# pcb3.net
KiCad netlist of a schematic drawn in EAGLE
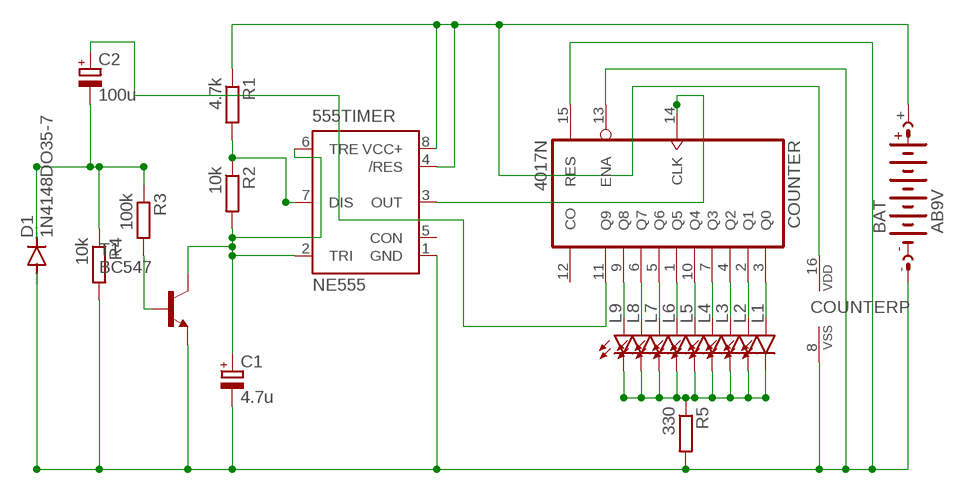
[diagram p0: schematic, sheet 1]

(export (version "E")
  (design (tool "Eeschema 10.0.6"))
  (components
    (comp (ref "555TIMER")
      (value "NE555")
      (footprint "eagle-import:DIL-08")
      (fields (field (name "MF") "Arrow Electronics") (field (name "MPN") "NE555N"))
      (libsource (lib "eagle-import") (part "NE555"))
    )
    (comp (ref "BAT")
      (value "AB9V")
      (footprint "eagle-import:AB9V")
      (libsource (lib "eagle-import") (part "AB9V"))
    )
    (comp (ref "C1")
      (value "4.7u")
      (footprint "eagle-import:E2,5-5")
      (libsource (lib "eagle-import") (part "CPOL-EUE2.5-5"))
    )
    (comp (ref "C2")
      (value "100u")
      (footprint "eagle-import:E2,5-5")
      (libsource (lib "eagle-import") (part "CPOL-EUE2.5-5"))
    )
    (comp (ref "COUNTER")
      (value "4017N")
      (footprint "eagle-import:DIL16")
      (libsource (lib "eagle-import") (part "4017N"))
    )
    (comp (ref "D1")
      (value "1N4148DO35-7")
      (footprint "eagle-import:DO35-7")
      (libsource (lib "eagle-import") (part "1N4148DO35-7"))
    )
    (comp (ref "L1")
      (value "LED5MM")
      (footprint "eagle-import:LED5MM")
      (libsource (lib "eagle-import") (part "LED5MM"))
    )
    (comp (ref "L2")
      (value "LED5MM")
      (footprint "eagle-import:LED5MM")
      (libsource (lib "eagle-import") (part "LED5MM"))
    )
    (comp (ref "L3")
      (value "LED5MM")
      (footprint "eagle-import:LED5MM")
      (libsource (lib "eagle-import") (part "LED5MM"))
    )
    (comp (ref "L4")
      (value "LED5MM")
      (footprint "eagle-import:LED5MM")
      (libsource (lib "eagle-import") (part "LED5MM"))
    )
    (comp (ref "L5")
      (value "LED5MM")
      (footprint "eagle-import:LED5MM")
      (libsource (lib "eagle-import") (part "LED5MM"))
    )
    (comp (ref "L6")
      (value "LED5MM")
      (footprint "eagle-import:LED5MM")
      (libsource (lib "eagle-import") (part "LED5MM"))
    )
    (comp (ref "L7")
      (value "LED5MM")
      (footprint "eagle-import:LED5MM")
      (libsource (lib "eagle-import") (part "LED5MM"))
    )
    (comp (ref "L8")
      (value "LED5MM")
      (footprint "eagle-import:LED5MM")
      (libsource (lib "eagle-import") (part "LED5MM"))
    )
    (comp (ref "L9")
      (value "LED5MM")
      (footprint "eagle-import:LED5MM")
      (libsource (lib "eagle-import") (part "LED5MM"))
    )
    (comp (ref "R1")
      (value "4.7k")
      (footprint "eagle-import:0207_10")
      (libsource (lib "eagle-import") (part "R-EU_0207/10"))
    )
    (comp (ref "R2")
      (value "10k")
      (footprint "eagle-import:0207_10")
      (libsource (lib "eagle-import") (part "R-EU_0207/10"))
    )
    (comp (ref "R3")
      (value "100k")
      (footprint "eagle-import:0207_10")
      (libsource (lib "eagle-import") (part "R-EU_0207/10"))
    )
    (comp (ref "R4")
      (value "10k")
      (footprint "eagle-import:0207_10")
      (libsource (lib "eagle-import") (part "R-EU_0207/10"))
    )
    (comp (ref "R5")
      (value "330")
      (footprint "eagle-import:0207_10")
      (libsource (lib "eagle-import") (part "R-EU_0207/10"))
    )
    (comp (ref "T1")
      (value "BC547")
      (footprint "eagle-import:TO92")
      (libsource (lib "eagle-import") (part "BC547"))
    )
  )
  (nets
    (net (code "1") (name "Net-(555TIMER-DIS)") (class "Default")
      (node (ref "555TIMER") (pin "7") (pinfunction "DIS_7") (pintype "input"))
      (node (ref "R1") (pin "2") (pinfunction "2_2") (pintype "passive"))
      (node (ref "R2") (pin "1") (pinfunction "1_1") (pintype "passive"))
    )
    (net (code "2") (name "Net-(555TIMER-GND)") (class "Default")
      (node (ref "555TIMER") (pin "1") (pinfunction "GND_1") (pintype "power_in"))
      (node (ref "BAT") (pin "-") (pinfunction "-_-") (pintype "passive"))
      (node (ref "C1") (pin "-") (pinfunction "-_-") (pintype "passive"))
      (node (ref "COUNTER") (pin "13") (pinfunction "ENA_13") (pintype "input"))
      (node (ref "COUNTER") (pin "15") (pinfunction "RES_15") (pintype "input"))
      (node (ref "COUNTER") (pin "8") (pinfunction "VSS_8") (pintype "power_in"))
      (node (ref "D1") (pin "A") (pinfunction "A_A") (pintype "passive"))
      (node (ref "R4") (pin "2") (pinfunction "2_2") (pintype "passive"))
      (node (ref "R5") (pin "2") (pinfunction "2_2") (pintype "passive"))
      (node (ref "T1") (pin "1") (pinfunction "E_1") (pintype "passive"))
    )
    (net (code "3") (name "Net-(555TIMER-OUT)") (class "Default")
      (node (ref "555TIMER") (pin "3") (pinfunction "OUT_3") (pintype "output"))
      (node (ref "COUNTER") (pin "14") (pinfunction "CLK_14") (pintype "input"))
    )
    (net (code "4") (name "Net-(555TIMER-TRE)") (class "Default")
      (node (ref "555TIMER") (pin "2") (pinfunction "TRI_2") (pintype "input"))
      (node (ref "555TIMER") (pin "6") (pinfunction "TRE_6") (pintype "input"))
      (node (ref "C1") (pin "+") (pinfunction "+_+") (pintype "passive"))
      (node (ref "R2") (pin "2") (pinfunction "2_2") (pintype "passive"))
      (node (ref "T1") (pin "3") (pinfunction "C_3") (pintype "passive"))
    )
    (net (code "5") (name "Net-(555TIMER-VCC+)") (class "Default")
      (node (ref "555TIMER") (pin "4") (pinfunction "/RES_4") (pintype "input"))
      (node (ref "555TIMER") (pin "8") (pinfunction "VCC+_8") (pintype "power_in"))
      (node (ref "BAT") (pin "+") (pinfunction "+_+") (pintype "passive"))
      (node (ref "COUNTER") (pin "16") (pinfunction "VDD_16") (pintype "power_in"))
      (node (ref "R1") (pin "1") (pinfunction "1_1") (pintype "passive"))
    )
    (net (code "6") (name "Net-(C2-Pad-)") (class "Default")
      (node (ref "C2") (pin "-") (pinfunction "-_-") (pintype "passive"))
      (node (ref "D1") (pin "C") (pinfunction "C_C") (pintype "passive"))
      (node (ref "R3") (pin "1") (pinfunction "1_1") (pintype "passive"))
      (node (ref "R4") (pin "1") (pinfunction "1_1") (pintype "passive"))
    )
    (net (code "7") (name "Net-(COUNTERA-Q0)") (class "Default")
      (node (ref "COUNTER") (pin "3") (pinfunction "Q0_3") (pintype "output"))
      (node (ref "L1") (pin "A") (pinfunction "A_A") (pintype "passive"))
    )
    (net (code "8") (name "Net-(COUNTERA-Q1)") (class "Default")
      (node (ref "COUNTER") (pin "2") (pinfunction "Q1_2") (pintype "output"))
      (node (ref "L2") (pin "A") (pinfunction "A_A") (pintype "passive"))
    )
    (net (code "9") (name "Net-(COUNTERA-Q2)") (class "Default")
      (node (ref "COUNTER") (pin "4") (pinfunction "Q2_4") (pintype "output"))
      (node (ref "L3") (pin "A") (pinfunction "A_A") (pintype "passive"))
    )
    (net (code "10") (name "Net-(COUNTERA-Q3)") (class "Default")
      (node (ref "COUNTER") (pin "7") (pinfunction "Q3_7") (pintype "output"))
      (node (ref "L4") (pin "A") (pinfunction "A_A") (pintype "passive"))
    )
    (net (code "11") (name "Net-(COUNTERA-Q4)") (class "Default")
      (node (ref "COUNTER") (pin "10") (pinfunction "Q4_10") (pintype "output"))
      (node (ref "L5") (pin "A") (pinfunction "A_A") (pintype "passive"))
    )
    (net (code "12") (name "Net-(COUNTERA-Q5)") (class "Default")
      (node (ref "COUNTER") (pin "1") (pinfunction "Q5_1") (pintype "output"))
      (node (ref "L6") (pin "A") (pinfunction "A_A") (pintype "passive"))
    )
    (net (code "13") (name "Net-(COUNTERA-Q6)") (class "Default")
      (node (ref "COUNTER") (pin "5") (pinfunction "Q6_5") (pintype "output"))
      (node (ref "L7") (pin "A") (pinfunction "A_A") (pintype "passive"))
    )
    (net (code "14") (name "Net-(COUNTERA-Q7)") (class "Default")
      (node (ref "COUNTER") (pin "6") (pinfunction "Q7_6") (pintype "output"))
      (node (ref "L8") (pin "A") (pinfunction "A_A") (pintype "passive"))
    )
    (net (code "15") (name "Net-(COUNTERA-Q8)") (class "Default")
      (node (ref "COUNTER") (pin "9") (pinfunction "Q8_9") (pintype "output"))
      (node (ref "L9") (pin "A") (pinfunction "A_A") (pintype "passive"))
    )
    (net (code "16") (name "Net-(COUNTERA-Q9)") (class "Default")
      (node (ref "C2") (pin "+") (pinfunction "+_+") (pintype "passive"))
      (node (ref "COUNTER") (pin "11") (pinfunction "Q9_11") (pintype "output"))
    )
    (net (code "17") (name "Net-(L1-C)") (class "Default")
      (node (ref "L1") (pin "K") (pinfunction "C_K") (pintype "passive"))
      (node (ref "L2") (pin "K") (pinfunction "C_K") (pintype "passive"))
      (node (ref "L3") (pin "K") (pinfunction "C_K") (pintype "passive"))
      (node (ref "L4") (pin "K") (pinfunction "C_K") (pintype "passive"))
      (node (ref "L5") (pin "K") (pinfunction "C_K") (pintype "passive"))
      (node (ref "L6") (pin "K") (pinfunction "C_K") (pintype "passive"))
      (node (ref "L7") (pin "K") (pinfunction "C_K") (pintype "passive"))
      (node (ref "L8") (pin "K") (pinfunction "C_K") (pintype "passive"))
      (node (ref "L9") (pin "K") (pinfunction "C_K") (pintype "passive"))
      (node (ref "R5") (pin "1") (pinfunction "1_1") (pintype "passive"))
    )
    (net (code "18") (name "Net-(T1-B)") (class "Default")
      (node (ref "R3") (pin "2") (pinfunction "2_2") (pintype "passive"))
      (node (ref "T1") (pin "2") (pinfunction "B_2") (pintype "passive"))
    )
    (net (code "19") (name "unconnected-(555TIMER-CON-Pad5)") (class "Default")
      (node (ref "555TIMER") (pin "5") (pinfunction "CON_5") (pintype "input"))
    )
    (net (code "20") (name "unconnected-(COUNTERA-CO-Pad12)") (class "Default")
      (node (ref "COUNTER") (pin "12") (pinfunction "CO_12") (pintype "output"))
    )
  )
)
